# Sheet1.net
KiCad netlist of a schematic drawn in Altium Designer
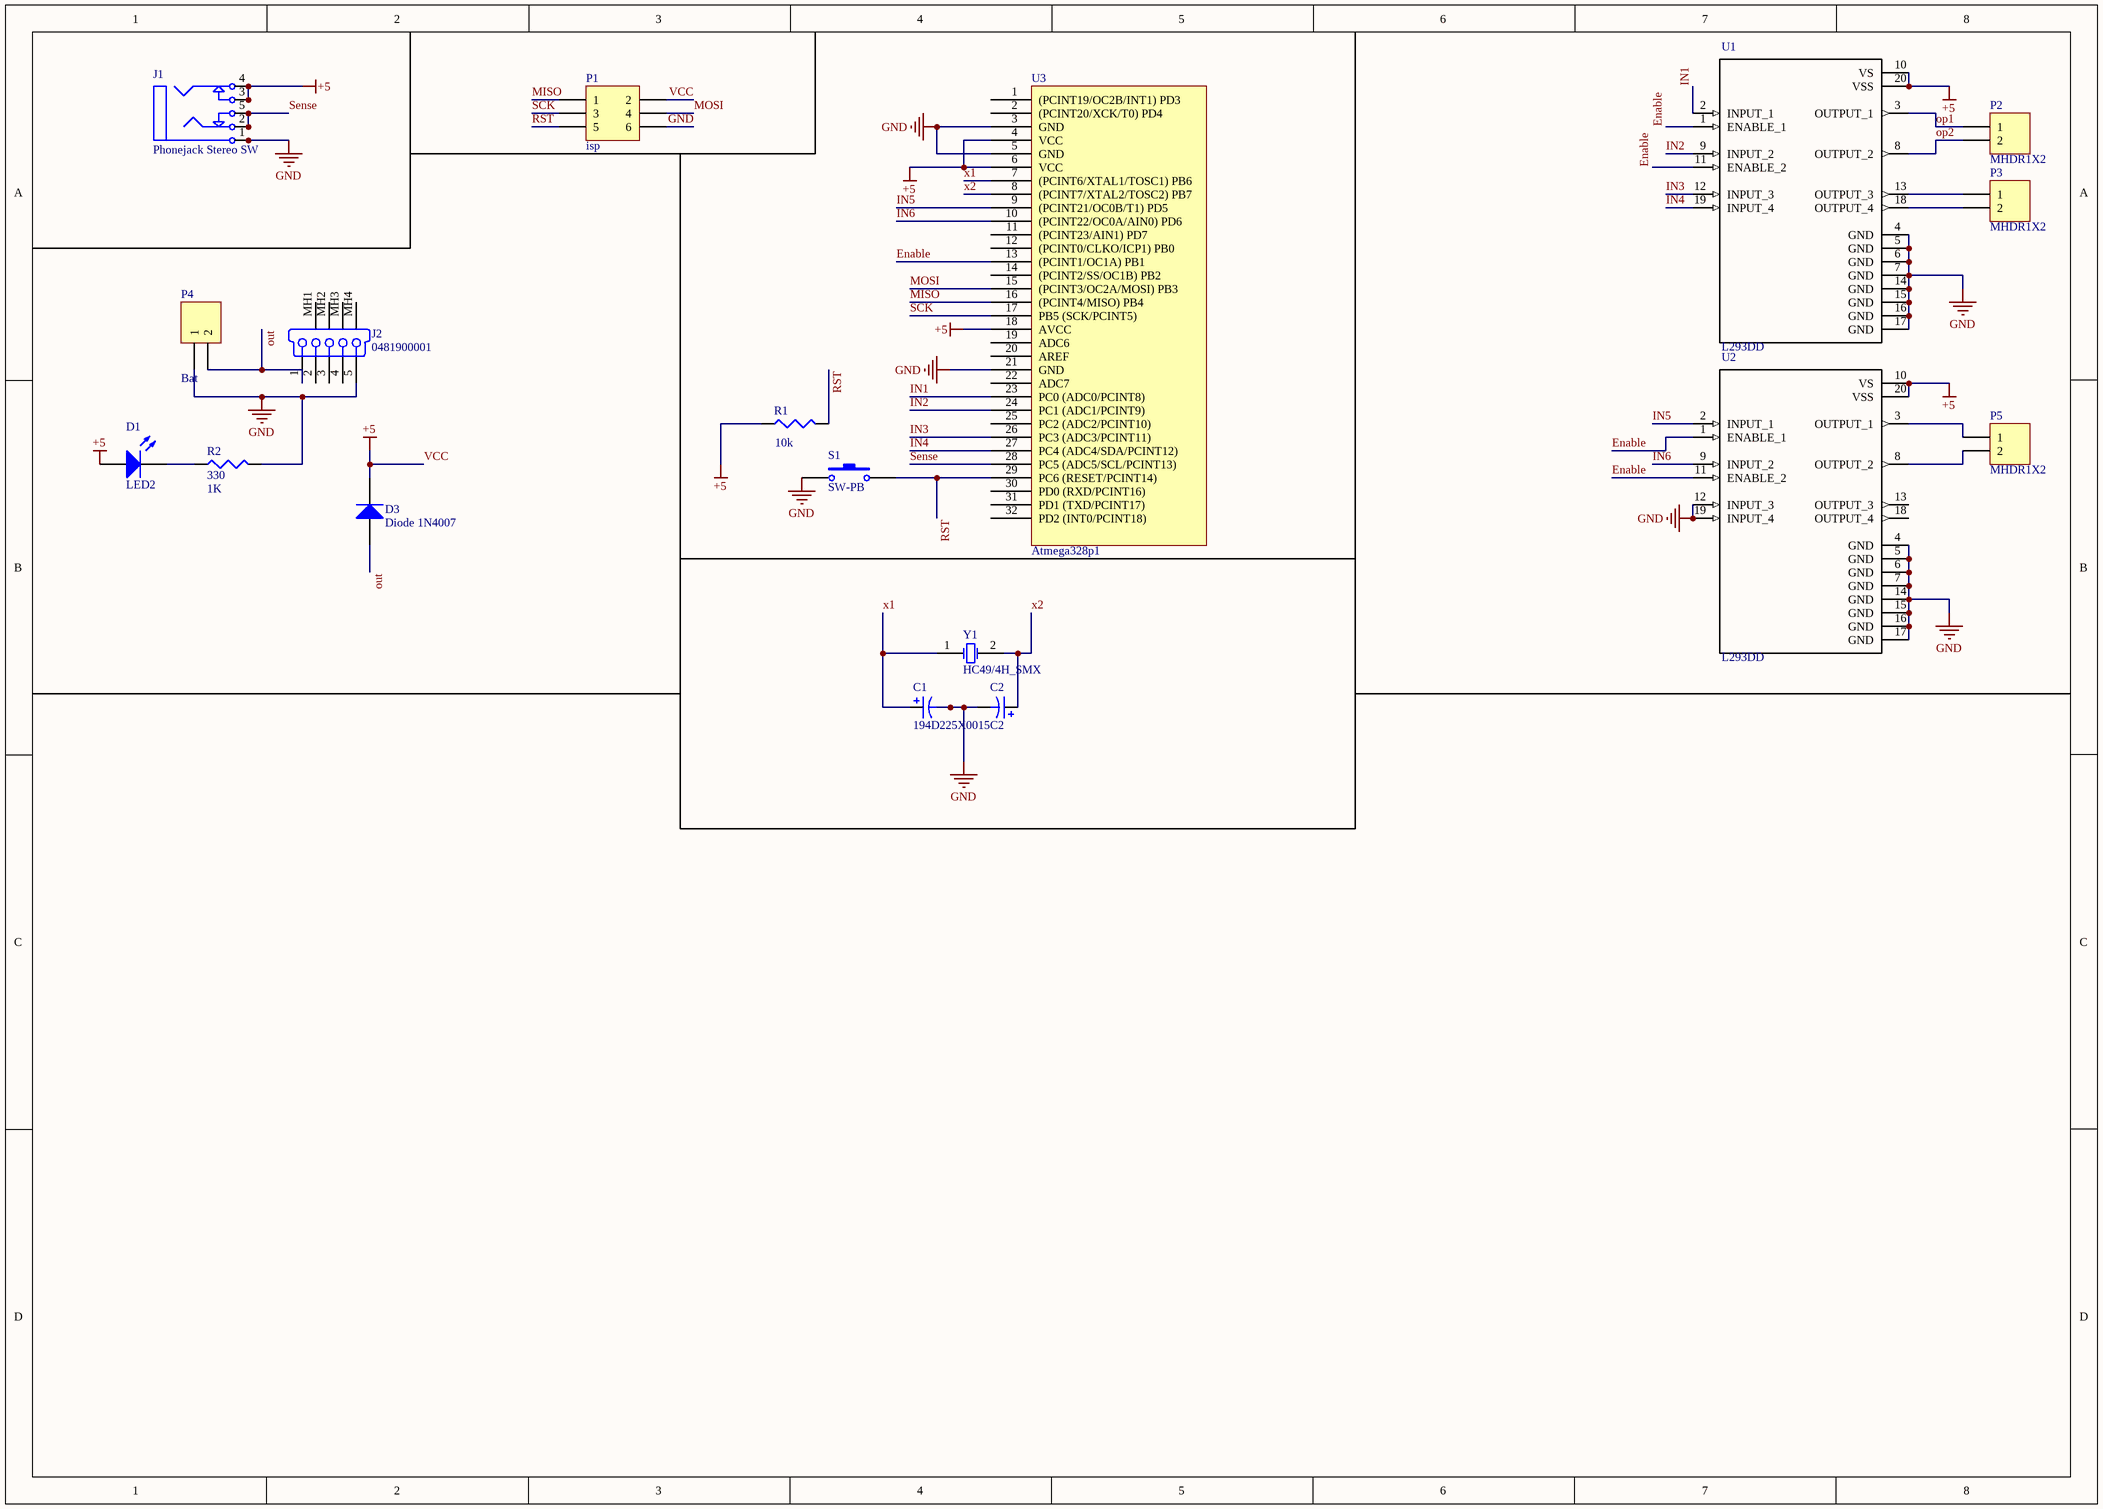
[diagram p0: Sheet1.SchDoc]

(export (version "E")
  (design (tool "Eeschema 10.0.6"))
  (components
    (comp (ref "C1")
      (value "194D225X0015C2")
      (footprint "C")
      (fields (field (name "PUBLISHER") "Altium Limited"))
      (libsource (lib "Vishay Sprague Tantalum Chip Capacitor") (part "194D225X0015C2"))
    )
    (comp (ref "C2")
      (value "~")
      (footprint "C")
      (fields (field (name "PUBLISHER") "Altium Limited"))
      (libsource (lib "Vishay Sprague Tantalum Chip Capacitor") (part "194D225X0015C2"))
    )
    (comp (ref "D1")
      (value "LED2")
      (footprint "3.2X1.6X1.1")
      (description "Typical RED, GREEN, YELLOW, AMBER GaAs LED")
      (fields (field (name "PUBLISHER") "Altium Limited"))
      (libsource (lib "Miscellaneous Devices") (part "LED2"))
    )
    (comp (ref "D3")
      (value "Diode 1N4007")
      (footprint "DO-41")
      (description "1 Amp General Purpose Rectifier")
      (fields (field (name "PUBLISHER") "Altium Limited"))
      (libsource (lib "Miscellaneous Devices") (part "Diode 1N4007"))
    )
    (comp (ref "J1")
      (value "Phonejack Stereo SW")
      (footprint "ST-3150-5N")
      (description "3-Conductor Jack with 2 break contacts (normals) and 2 auxiliary make contacts")
      (fields (field (name "PUBLISHER") "Altium Limited"))
      (libsource (lib "Miscellaneous Connectors") (part "Phonejack Stereo SW"))
    )
    (comp (ref "J2")
      (value "0481900001")
      (footprint "481900001")
      (fields (field (name "PUBLISHER") "Altium Limited"))
      (libsource (lib "Molex Serial Bus Mini USB") (part "0481900001"))
    )
    (comp (ref "P1")
      (value "isp")
      (footprint "HDR2X3")
      (description "Header, 3-Pin, Dual row")
      (fields (field (name "PUBLISHER") "Altium Limited"))
      (libsource (lib "Miscellaneous Connectors") (part "Header 3X2"))
    )
    (comp (ref "P2")
      (value "MHDR1X2")
      (footprint "MHDR1X2")
      (description "Header, 2-Pin")
      (fields (field (name "PUBLISHER") "Altium Limited"))
      (libsource (lib "Miscellaneous Connectors") (part "MHDR1X2"))
    )
    (comp (ref "P3")
      (value "MHDR1X2")
      (footprint "MHDR1X2")
      (description "Header, 2-Pin")
      (fields (field (name "PUBLISHER") "Altium Limited"))
      (libsource (lib "Miscellaneous Connectors") (part "MHDR1X2"))
    )
    (comp (ref "P4")
      (value "Bat")
      (footprint "MHDR1X2")
      (description "Header, 2-Pin")
      (fields (field (name "PUBLISHER") "Altium Limited"))
      (libsource (lib "") (part "MHDR1X2_1"))
    )
    (comp (ref "P5")
      (value "MHDR1X2")
      (footprint "MHDR1X2")
      (description "Header, 2-Pin")
      (fields (field (name "PUBLISHER") "Altium Limited"))
      (libsource (lib "Miscellaneous Connectors") (part "MHDR1X2"))
    )
    (comp (ref "R1")
      (value "10k")
      (footprint "12Z-2010")
      (description "Resistor")
      (fields (field (name "PUBLISHER") "Altium Limited"))
      (libsource (lib "Miscellaneous Devices") (part "Res3"))
    )
    (comp (ref "R2")
      (value "330")
      (footprint "12Z-2010")
      (description "Resistor")
      (fields (field (name "ALTIUM_VALUE") "1K") (field (name "PUBLISHER") "Altium Limited"))
      (libsource (lib "Miscellaneous Devices") (part "Res3"))
    )
    (comp (ref "S1")
      (value "SW-PB")
      (footprint "SPST-2")
      (description "Switch")
      (fields (field (name "PUBLISHER") "Altium Limited"))
      (libsource (lib "Miscellaneous Devices") (part "SW-PB"))
    )
    (comp (ref "U1")
      (value "L293DD")
      (footprint "*SOIC127P1032X265-20N")
      (description "L293DD Series Push - Pull Quad Channel Driver with Diodes - SOIC-20")
      (fields (field (name "MF") "STMicroelectronics"))
      (libsource (lib "L293DD") (part "L293DD"))
    )
    (comp (ref "U2")
      (value "L293DD")
      (footprint "*SOIC127P1032X265-20N")
      (description "L293DD Series Push - Pull Quad Channel Driver with Diodes - SOIC-20")
      (fields (field (name "MF") "STMicroelectronics"))
      (libsource (lib "L293DD") (part "L293DD"))
    )
    (comp (ref "U3")
      (value "Atmega328p1")
      (footprint "TQFP80P900X900X120-32N")
      (description "AVR")
      (libsource (lib "123p") (part "Atmega328p1"))
    )
    (comp (ref "Y1")
      (value "HC49/4H_SMX")
      (footprint "HC49/4H_SMX")
      (description "Surface Mount Quartz Crystal")
      (fields (field (name "PUBLISHER") "Altium Limited"))
      (libsource (lib "C-MAC Crystal Oscillator") (part "HC49/4H_SMX"))
    )
  )
  (nets
    (net (code "1") (name "+5") (class "Default")
      (node (ref "D1") (pin "1") (pinfunction "A_1") (pintype "passive"))
      (node (ref "D3") (pin "2") (pinfunction "K_2") (pintype "passive"))
      (node (ref "J1") (pin "3") (pinfunction "3_3") (pintype "passive"))
      (node (ref "J1") (pin "3A") (pinfunction "3A_3A") (pintype "passive"))
      (node (ref "J1") (pin "3B") (pinfunction "3B_3B") (pintype "passive"))
      (node (ref "J1") (pin "4") (pinfunction "4_4") (pintype "passive"))
      (node (ref "J1") (pin "4A") (pinfunction "4A_4A") (pintype "passive"))
      (node (ref "J1") (pin "4B") (pinfunction "4B_4B") (pintype "passive"))
      (node (ref "P1") (pin "2") (pinfunction "2_2") (pintype "passive"))
      (node (ref "R1") (pin "1") (pinfunction "1_1") (pintype "passive"))
      (node (ref "U1") (pin "10") (pinfunction "VS_10") (pintype "power_in"))
      (node (ref "U1") (pin "20") (pinfunction "VSS_20") (pintype "power_in"))
      (node (ref "U2") (pin "10") (pinfunction "VS_10") (pintype "power_in"))
      (node (ref "U2") (pin "20") (pinfunction "VSS_20") (pintype "power_in"))
      (node (ref "U3") (pin "18") (pinfunction "AVCC_18") (pintype "passive"))
      (node (ref "U3") (pin "4") (pinfunction "VCC_4") (pintype "passive"))
      (node (ref "U3") (pin "6") (pinfunction "VCC_6") (pintype "passive"))
    )
    (net (code "2") (name "/Enable") (class "Default")
      (node (ref "U1") (pin "1") (pinfunction "ENABLE_1_1") (pintype "input"))
      (node (ref "U1") (pin "11") (pinfunction "ENABLE_2_11") (pintype "input"))
      (node (ref "U2") (pin "1") (pinfunction "ENABLE_1_1") (pintype "input"))
      (node (ref "U2") (pin "11") (pinfunction "ENABLE_2_11") (pintype "input"))
      (node (ref "U3") (pin "13") (pinfunction "(PCINT1/OC1A)_PB1_13") (pintype "passive"))
    )
    (net (code "3") (name "/IN1") (class "Default")
      (node (ref "U1") (pin "2") (pinfunction "INPUT_1_2") (pintype "input"))
      (node (ref "U3") (pin "23") (pinfunction "PC0_(ADC0/PCINT8)_23") (pintype "passive"))
    )
    (net (code "4") (name "/IN2") (class "Default")
      (node (ref "U1") (pin "9") (pinfunction "INPUT_2_9") (pintype "input"))
      (node (ref "U3") (pin "24") (pinfunction "PC1_(ADC1/PCINT9)_24") (pintype "passive"))
    )
    (net (code "5") (name "/IN3") (class "Default")
      (node (ref "U1") (pin "12") (pinfunction "INPUT_3_12") (pintype "input"))
      (node (ref "U3") (pin "26") (pinfunction "PC3_(ADC3/PCINT11)_26") (pintype "passive"))
    )
    (net (code "6") (name "/IN4") (class "Default")
      (node (ref "U1") (pin "19") (pinfunction "INPUT_4_19") (pintype "input"))
      (node (ref "U3") (pin "27") (pinfunction "PC4_(ADC4/SDA/PCINT12)_27") (pintype "passive"))
    )
    (net (code "7") (name "/IN5") (class "Default")
      (node (ref "U2") (pin "2") (pinfunction "INPUT_1_2") (pintype "input"))
      (node (ref "U3") (pin "9") (pinfunction "(PCINT21/OC0B/T1)_PD5_9") (pintype "passive"))
    )
    (net (code "8") (name "/IN6") (class "Default")
      (node (ref "U2") (pin "9") (pinfunction "INPUT_2_9") (pintype "input"))
      (node (ref "U3") (pin "10") (pinfunction "(PCINT22/OC0A/AIN0)_PD6_10") (pintype "passive"))
    )
    (net (code "9") (name "/MISO") (class "Default")
      (node (ref "P1") (pin "1") (pinfunction "1_1") (pintype "passive"))
      (node (ref "U3") (pin "16") (pinfunction "(PCINT4/MISO)_PB4_16") (pintype "passive"))
    )
    (net (code "10") (name "/MOSI") (class "Default")
      (node (ref "P1") (pin "4") (pinfunction "4_4") (pintype "passive"))
      (node (ref "U3") (pin "15") (pinfunction "(PCINT3/OC2A/MOSI)_PB3_15") (pintype "passive"))
    )
    (net (code "11") (name "/RST") (class "Default")
      (node (ref "P1") (pin "5") (pinfunction "5_5") (pintype "passive"))
      (node (ref "R1") (pin "2") (pinfunction "2_2") (pintype "passive"))
      (node (ref "S1") (pin "2") (pinfunction "2_2") (pintype "passive"))
      (node (ref "U3") (pin "29") (pinfunction "PC6_(RESET/PCINT14)_29") (pintype "passive"))
    )
    (net (code "12") (name "/SCK") (class "Default")
      (node (ref "P1") (pin "3") (pinfunction "3_3") (pintype "passive"))
      (node (ref "U3") (pin "17") (pinfunction "PB5_(SCK/PCINT5)_17") (pintype "passive"))
    )
    (net (code "13") (name "/Sense") (class "Default")
      (node (ref "J1") (pin "2") (pinfunction "2_2") (pintype "passive"))
      (node (ref "J1") (pin "2A") (pinfunction "2A_2A") (pintype "passive"))
      (node (ref "J1") (pin "2B") (pinfunction "2B_2B") (pintype "passive"))
      (node (ref "J1") (pin "5") (pinfunction "5_5") (pintype "passive"))
      (node (ref "J1") (pin "5A") (pinfunction "5A_5A") (pintype "passive"))
      (node (ref "J1") (pin "5B") (pinfunction "5B_5B") (pintype "passive"))
      (node (ref "U3") (pin "28") (pinfunction "PC5_(ADC5/SCL/PCINT13)_28") (pintype "passive"))
    )
    (net (code "14") (name "/op1") (class "Default")
      (node (ref "P2") (pin "1") (pinfunction "1_1") (pintype "passive"))
      (node (ref "U1") (pin "3") (pinfunction "OUTPUT_1_3") (pintype "output"))
    )
    (net (code "15") (name "/op2") (class "Default")
      (node (ref "P2") (pin "2") (pinfunction "2_2") (pintype "passive"))
      (node (ref "U1") (pin "8") (pinfunction "OUTPUT_2_8") (pintype "output"))
    )
    (net (code "16") (name "/out") (class "Default")
      (node (ref "D3") (pin "1") (pinfunction "A_1") (pintype "passive"))
      (node (ref "J2") (pin "1") (pinfunction "V_BUS_(5V)_1") (pintype "passive"))
      (node (ref "P4") (pin "2") (pinfunction "2_2") (pintype "passive"))
    )
    (net (code "17") (name "/x1") (class "Default")
      (node (ref "C1") (pin "1") (pinfunction "1_1") (pintype "passive"))
      (node (ref "U3") (pin "7") (pinfunction "(PCINT6/XTAL1/TOSC1)_PB6_7") (pintype "passive"))
      (node (ref "Y1") (pin "1") (pinfunction "OSC1_1") (pintype "passive"))
    )
    (net (code "18") (name "/x2") (class "Default")
      (node (ref "C2") (pin "1") (pinfunction "1_1") (pintype "passive"))
      (node (ref "U3") (pin "8") (pinfunction "(PCINT7/XTAL2/TOSC2)_PB7_8") (pintype "passive"))
      (node (ref "Y1") (pin "2") (pinfunction "OSC2_2") (pintype "passive"))
    )
    (net (code "19") (name "GND") (class "Default")
      (node (ref "C1") (pin "2") (pinfunction "2_2") (pintype "passive"))
      (node (ref "C2") (pin "2") (pinfunction "2_2") (pintype "passive"))
      (node (ref "J1") (pin "1") (pinfunction "1_1") (pintype "passive"))
      (node (ref "J1") (pin "1A") (pinfunction "1A_1A") (pintype "passive"))
      (node (ref "J1") (pin "1B") (pinfunction "1B_1B") (pintype "passive"))
      (node (ref "J2") (pin "5") (pinfunction "GND_5") (pintype "passive"))
      (node (ref "P1") (pin "6") (pinfunction "6_6") (pintype "passive"))
      (node (ref "P4") (pin "1") (pinfunction "1_1") (pintype "passive"))
      (node (ref "R2") (pin "2") (pinfunction "2_2") (pintype "passive"))
      (node (ref "S1") (pin "1") (pinfunction "1_1") (pintype "passive"))
      (node (ref "U1") (pin "14") (pinfunction "GND_14") (pintype "power_in"))
      (node (ref "U1") (pin "15") (pinfunction "GND_15") (pintype "power_in"))
      (node (ref "U1") (pin "16") (pinfunction "GND_16") (pintype "power_in"))
      (node (ref "U1") (pin "17") (pinfunction "GND_17") (pintype "power_in"))
      (node (ref "U1") (pin "4") (pinfunction "GND_4") (pintype "power_in"))
      (node (ref "U1") (pin "5") (pinfunction "GND_5") (pintype "power_in"))
      (node (ref "U1") (pin "6") (pinfunction "GND_6") (pintype "power_in"))
      (node (ref "U1") (pin "7") (pinfunction "GND_7") (pintype "power_in"))
      (node (ref "U2") (pin "12") (pinfunction "INPUT_3_12") (pintype "input"))
      (node (ref "U2") (pin "14") (pinfunction "GND_14") (pintype "power_in"))
      (node (ref "U2") (pin "15") (pinfunction "GND_15") (pintype "power_in"))
      (node (ref "U2") (pin "16") (pinfunction "GND_16") (pintype "power_in"))
      (node (ref "U2") (pin "17") (pinfunction "GND_17") (pintype "power_in"))
      (node (ref "U2") (pin "19") (pinfunction "INPUT_4_19") (pintype "input"))
      (node (ref "U2") (pin "4") (pinfunction "GND_4") (pintype "power_in"))
      (node (ref "U2") (pin "5") (pinfunction "GND_5") (pintype "power_in"))
      (node (ref "U2") (pin "6") (pinfunction "GND_6") (pintype "power_in"))
      (node (ref "U2") (pin "7") (pinfunction "GND_7") (pintype "power_in"))
      (node (ref "U3") (pin "21") (pinfunction "GND_21") (pintype "passive"))
      (node (ref "U3") (pin "3") (pinfunction "GND_3") (pintype "passive"))
      (node (ref "U3") (pin "5") (pinfunction "GND_5") (pintype "passive"))
    )
    (net (code "20") (name "Net-(D1-K)") (class "Default")
      (node (ref "D1") (pin "2") (pinfunction "K_2") (pintype "passive"))
      (node (ref "R2") (pin "1") (pinfunction "1_1") (pintype "passive"))
    )
    (net (code "21") (name "Net-(U1-OUTPUT_3)") (class "Default")
      (node (ref "P3") (pin "1") (pinfunction "1_1") (pintype "passive"))
      (node (ref "U1") (pin "13") (pinfunction "OUTPUT_3_13") (pintype "output"))
    )
    (net (code "22") (name "Net-(U1-OUTPUT_4)") (class "Default")
      (node (ref "P3") (pin "2") (pinfunction "2_2") (pintype "passive"))
      (node (ref "U1") (pin "18") (pinfunction "OUTPUT_4_18") (pintype "output"))
    )
    (net (code "23") (name "Net-(U2-OUTPUT_1)") (class "Default")
      (node (ref "P5") (pin "1") (pinfunction "1_1") (pintype "passive"))
      (node (ref "U2") (pin "3") (pinfunction "OUTPUT_1_3") (pintype "output"))
    )
    (net (code "24") (name "Net-(U2-OUTPUT_2)") (class "Default")
      (node (ref "P5") (pin "2") (pinfunction "2_2") (pintype "passive"))
      (node (ref "U2") (pin "8") (pinfunction "OUTPUT_2_8") (pintype "output"))
    )
    (net (code "25") (name "unconnected-(J2-D+-Pad3)") (class "Default")
      (node (ref "J2") (pin "3") (pinfunction "D+_3") (pintype "passive"))
    )
    (net (code "26") (name "unconnected-(J2-D--Pad2)") (class "Default")
      (node (ref "J2") (pin "2") (pinfunction "D-_2") (pintype "passive"))
    )
    (net (code "27") (name "unconnected-(J2-NC-Pad4)") (class "Default")
      (node (ref "J2") (pin "4") (pinfunction "NC_4") (pintype "passive"))
    )
    (net (code "28") (name "unconnected-(J2-Tab-PadMH1)") (class "Default")
      (node (ref "J2") (pin "MH1") (pinfunction "Tab_MH1") (pintype "passive"))
    )
    (net (code "29") (name "unconnected-(J2-Tab-PadMH2)") (class "Default")
      (node (ref "J2") (pin "MH2") (pinfunction "Tab_MH2") (pintype "passive"))
    )
    (net (code "30") (name "unconnected-(J2-Tab-PadMH3)") (class "Default")
      (node (ref "J2") (pin "MH3") (pinfunction "Tab_MH3") (pintype "passive"))
    )
    (net (code "31") (name "unconnected-(J2-Tab-PadMH4)") (class "Default")
      (node (ref "J2") (pin "MH4") (pinfunction "Tab_MH4") (pintype "passive"))
    )
    (net (code "32") (name "unconnected-(U2-OUTPUT_3-Pad13)") (class "Default")
      (node (ref "U2") (pin "13") (pinfunction "OUTPUT_3_13") (pintype "output"))
    )
    (net (code "33") (name "unconnected-(U2-OUTPUT_4-Pad18)") (class "Default")
      (node (ref "U2") (pin "18") (pinfunction "OUTPUT_4_18") (pintype "output"))
    )
    (net (code "34") (name "unconnected-(U3-(PCINT0{slash}CLKO{slash}ICP1)_PB0-Pad12)") (class "Default")
      (node (ref "U3") (pin "12") (pinfunction "(PCINT0/CLKO/ICP1)_PB0_12") (pintype "passive"))
    )
    (net (code "35") (name "unconnected-(U3-(PCINT2{slash}SS{slash}OC1B)_PB2-Pad14)") (class "Default")
      (node (ref "U3") (pin "14") (pinfunction "(PCINT2/SS/OC1B)_PB2_14") (pintype "passive"))
    )
    (net (code "36") (name "unconnected-(U3-(PCINT19{slash}OC2B{slash}INT1)_PD3-Pad1)") (class "Default")
      (node (ref "U3") (pin "1") (pinfunction "(PCINT19/OC2B/INT1)_PD3_1") (pintype "passive"))
    )
    (net (code "37") (name "unconnected-(U3-(PCINT20{slash}XCK{slash}T0)_PD4-Pad2)") (class "Default")
      (node (ref "U3") (pin "2") (pinfunction "(PCINT20/XCK/T0)_PD4_2") (pintype "passive"))
    )
    (net (code "38") (name "unconnected-(U3-(PCINT23{slash}AIN1)_PD7-Pad11)") (class "Default")
      (node (ref "U3") (pin "11") (pinfunction "(PCINT23/AIN1)_PD7_11") (pintype "passive"))
    )
    (net (code "39") (name "unconnected-(U3-ADC6-Pad19)") (class "Default")
      (node (ref "U3") (pin "19") (pinfunction "ADC6_19") (pintype "passive"))
    )
    (net (code "40") (name "unconnected-(U3-ADC7-Pad22)") (class "Default")
      (node (ref "U3") (pin "22") (pinfunction "ADC7_22") (pintype "passive"))
    )
    (net (code "41") (name "unconnected-(U3-AREF-Pad20)") (class "Default")
      (node (ref "U3") (pin "20") (pinfunction "AREF_20") (pintype "passive"))
    )
    (net (code "42") (name "unconnected-(U3-PC2_(ADC2{slash}PCINT10)-Pad25)") (class "Default")
      (node (ref "U3") (pin "25") (pinfunction "PC2_(ADC2/PCINT10)_25") (pintype "passive"))
    )
    (net (code "43") (name "unconnected-(U3-PD0_(RXD{slash}PCINT16)-Pad30)") (class "Default")
      (node (ref "U3") (pin "30") (pinfunction "PD0_(RXD/PCINT16)_30") (pintype "passive"))
    )
    (net (code "44") (name "unconnected-(U3-PD1_(TXD{slash}PCINT17)-Pad31)") (class "Default")
      (node (ref "U3") (pin "31") (pinfunction "PD1_(TXD/PCINT17)_31") (pintype "passive"))
    )
    (net (code "45") (name "unconnected-(U3-PD2_(INT0{slash}PCINT18)-Pad32)") (class "Default")
      (node (ref "U3") (pin "32") (pinfunction "PD2_(INT0/PCINT18)_32") (pintype "passive"))
    )
  )
)
